# MK1.net
KiCad netlist of a schematic drawn in Altium Designer
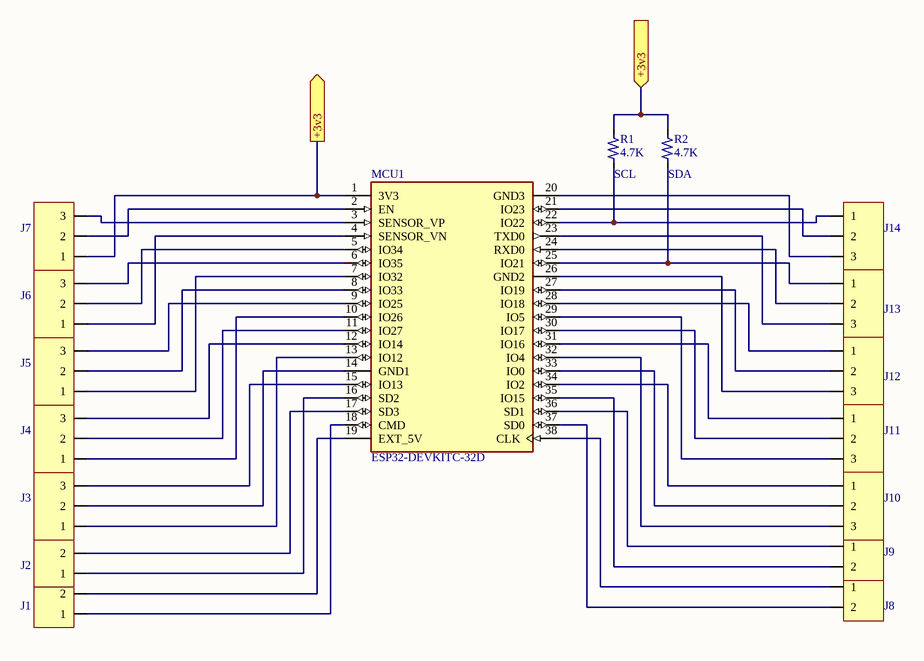
[diagram p0: MK1.SchDoc]

(export (version "E")
  (design (tool "Eeschema 10.0.6"))
  (components
    (comp (ref "J1")
      (value "~")
      (footprint "TB_200Mil 2 P")
      (libsource (lib "Library Connector") (part "TB 2 PIN"))
    )
    (comp (ref "J2")
      (value "~")
      (footprint "TB_200Mil 2 P")
      (libsource (lib "Library Connector") (part "TB 2 PIN"))
    )
    (comp (ref "J3") (value "~") (footprint "TB_200Mil 3 P") (libsource (lib "") (part "TB 3 PIN_1")))
    (comp (ref "J4") (value "~") (footprint "TB_200Mil 3 P") (libsource (lib "") (part "TB 3 PIN_1")))
    (comp (ref "J5") (value "~") (footprint "TB_200Mil 3 P") (libsource (lib "") (part "TB 3 PIN_1")))
    (comp (ref "J6") (value "~") (footprint "TB_200Mil 3 P") (libsource (lib "") (part "TB 3 PIN_1")))
    (comp (ref "J7") (value "~") (footprint "TB_200Mil 3 P") (libsource (lib "") (part "TB 3 PIN_1")))
    (comp (ref "J8") (value "~") (footprint "TB_200Mil 2 P") (libsource (lib "") (part "TB 2 PIN_1")))
    (comp (ref "J9") (value "~") (footprint "TB_200Mil 2 P") (libsource (lib "") (part "TB 2 PIN_1")))
    (comp (ref "J10")
      (value "~")
      (footprint "TB_200Mil 3 P")
      (libsource (lib "Library Connector") (part "TB 3 PIN"))
    )
    (comp (ref "J11")
      (value "~")
      (footprint "TB_200Mil 3 P")
      (libsource (lib "Library Connector") (part "TB 3 PIN"))
    )
    (comp (ref "J12")
      (value "~")
      (footprint "TB_200Mil 3 P")
      (libsource (lib "Library Connector") (part "TB 3 PIN"))
    )
    (comp (ref "J13")
      (value "~")
      (footprint "TB_200Mil 3 P")
      (libsource (lib "Library Connector") (part "TB 3 PIN"))
    )
    (comp (ref "J14")
      (value "~")
      (footprint "TB_200Mil 3 P")
      (libsource (lib "Library Connector") (part "TB 3 PIN"))
    )
    (comp (ref "MCU1")
      (value "ESP32-DEVKITC-32D")
      (footprint "MODULE_ESP32-DEVKITC-32D")
      (description "EVAL BOARD FOR ESP-WROOM-32")
      (fields (field (name "MF") "Espressif Systems"))
      (libsource (lib "ESP32-DEVKITC-32D") (part "ESP32-DEVKITC-32D"))
    )
    (comp (ref "R1") (value "4.7K") (footprint "4.7K") (libsource (lib "Library 0.25w 1_") (part "4.7K")))
    (comp (ref "R2") (value "4.7K") (footprint "4.7K") (libsource (lib "Library 0.25w 1_") (part "4.7K")))
  )
  (nets
    (net (code "1") (name "/+3v3") (class "Default")
      (node (ref "J7") (pin "1") (pinfunction "1_1") (pintype "passive"))
      (node (ref "MCU1") (pin "1") (pinfunction "3V3_1") (pintype "power_in"))
      (node (ref "R1") (pin "2") (pintype "passive"))
      (node (ref "R2") (pin "2") (pintype "passive"))
    )
    (net (code "2") (name "Net-(MCU1-CLK)") (class "Default")
      (node (ref "J8") (pin "1") (pinfunction "1_1") (pintype "passive"))
      (node (ref "MCU1") (pin "38") (pinfunction "CLK_38") (pintype "input"))
    )
    (net (code "3") (name "Net-(MCU1-CMD)") (class "Default")
      (node (ref "J1") (pin "1") (pinfunction "1_1") (pintype "passive"))
      (node (ref "MCU1") (pin "18") (pinfunction "CMD_18") (pintype "bidirectional"))
    )
    (net (code "4") (name "Net-(MCU1-EN)") (class "Default")
      (node (ref "J7") (pin "2") (pinfunction "2_2") (pintype "passive"))
      (node (ref "MCU1") (pin "2") (pinfunction "EN_2") (pintype "input"))
    )
    (net (code "5") (name "Net-(MCU1-EXT_5V)") (class "Default")
      (node (ref "J1") (pin "2") (pinfunction "2_2") (pintype "passive"))
      (node (ref "MCU1") (pin "19") (pinfunction "EXT_5V_19") (pintype "power_in"))
    )
    (net (code "6") (name "Net-(MCU1-GND1)") (class "Default")
      (node (ref "J3") (pin "2") (pinfunction "2_2") (pintype "passive"))
      (node (ref "MCU1") (pin "14") (pinfunction "GND1_14") (pintype "power_in"))
    )
    (net (code "7") (name "Net-(MCU1-GND2)") (class "Default")
      (node (ref "J12") (pin "3") (pinfunction "3_3") (pintype "passive"))
      (node (ref "MCU1") (pin "26") (pinfunction "GND2_26") (pintype "power_in"))
    )
    (net (code "8") (name "Net-(MCU1-GND3)") (class "Default")
      (node (ref "J14") (pin "3") (pinfunction "3_3") (pintype "passive"))
      (node (ref "MCU1") (pin "20") (pinfunction "GND3_20") (pintype "power_in"))
    )
    (net (code "9") (name "Net-(MCU1-IO0)") (class "Default")
      (node (ref "J10") (pin "2") (pinfunction "2_2") (pintype "passive"))
      (node (ref "MCU1") (pin "33") (pinfunction "IO0_33") (pintype "bidirectional"))
    )
    (net (code "10") (name "Net-(MCU1-IO2)") (class "Default")
      (node (ref "J10") (pin "1") (pinfunction "1_1") (pintype "passive"))
      (node (ref "MCU1") (pin "34") (pinfunction "IO2_34") (pintype "bidirectional"))
    )
    (net (code "11") (name "Net-(MCU1-IO4)") (class "Default")
      (node (ref "J10") (pin "3") (pinfunction "3_3") (pintype "passive"))
      (node (ref "MCU1") (pin "32") (pinfunction "IO4_32") (pintype "bidirectional"))
    )
    (net (code "12") (name "Net-(MCU1-IO5)") (class "Default")
      (node (ref "J11") (pin "3") (pinfunction "3_3") (pintype "passive"))
      (node (ref "MCU1") (pin "29") (pinfunction "IO5_29") (pintype "bidirectional"))
    )
    (net (code "13") (name "Net-(MCU1-IO12)") (class "Default")
      (node (ref "J3") (pin "1") (pinfunction "1_1") (pintype "passive"))
      (node (ref "MCU1") (pin "13") (pinfunction "IO12_13") (pintype "bidirectional"))
    )
    (net (code "14") (name "Net-(MCU1-IO13)") (class "Default")
      (node (ref "J3") (pin "3") (pinfunction "3_3") (pintype "passive"))
      (node (ref "MCU1") (pin "15") (pinfunction "IO13_15") (pintype "bidirectional"))
    )
    (net (code "15") (name "Net-(MCU1-IO14)") (class "Default")
      (node (ref "J4") (pin "3") (pinfunction "3_3") (pintype "passive"))
      (node (ref "MCU1") (pin "12") (pinfunction "IO14_12") (pintype "bidirectional"))
    )
    (net (code "16") (name "Net-(MCU1-IO15)") (class "Default")
      (node (ref "J9") (pin "2") (pinfunction "2_2") (pintype "passive"))
      (node (ref "MCU1") (pin "35") (pinfunction "IO15_35") (pintype "bidirectional"))
    )
    (net (code "17") (name "Net-(MCU1-IO16)") (class "Default")
      (node (ref "J11") (pin "1") (pinfunction "1_1") (pintype "passive"))
      (node (ref "MCU1") (pin "31") (pinfunction "IO16_31") (pintype "bidirectional"))
    )
    (net (code "18") (name "Net-(MCU1-IO17)") (class "Default")
      (node (ref "J11") (pin "2") (pinfunction "2_2") (pintype "passive"))
      (node (ref "MCU1") (pin "30") (pinfunction "IO17_30") (pintype "bidirectional"))
    )
    (net (code "19") (name "Net-(MCU1-IO18)") (class "Default")
      (node (ref "J12") (pin "1") (pinfunction "1_1") (pintype "passive"))
      (node (ref "MCU1") (pin "28") (pinfunction "IO18_28") (pintype "bidirectional"))
    )
    (net (code "20") (name "Net-(MCU1-IO19)") (class "Default")
      (node (ref "J12") (pin "2") (pinfunction "2_2") (pintype "passive"))
      (node (ref "MCU1") (pin "27") (pinfunction "IO19_27") (pintype "bidirectional"))
    )
    (net (code "21") (name "Net-(MCU1-IO21)") (class "Default")
      (node (ref "J13") (pin "1") (pinfunction "1_1") (pintype "passive"))
      (node (ref "MCU1") (pin "25") (pinfunction "IO21_25") (pintype "bidirectional"))
      (node (ref "R2") (pin "1") (pintype "passive"))
    )
    (net (code "22") (name "Net-(MCU1-IO22)") (class "Default")
      (node (ref "J14") (pin "1") (pinfunction "1_1") (pintype "passive"))
      (node (ref "MCU1") (pin "22") (pinfunction "IO22_22") (pintype "bidirectional"))
      (node (ref "R1") (pin "1") (pintype "passive"))
    )
    (net (code "23") (name "Net-(MCU1-IO23)") (class "Default")
      (node (ref "J14") (pin "2") (pinfunction "2_2") (pintype "passive"))
      (node (ref "MCU1") (pin "21") (pinfunction "IO23_21") (pintype "bidirectional"))
    )
    (net (code "24") (name "Net-(MCU1-IO25)") (class "Default")
      (node (ref "J5") (pin "3") (pinfunction "3_3") (pintype "passive"))
      (node (ref "MCU1") (pin "9") (pinfunction "IO25_9") (pintype "bidirectional"))
    )
    (net (code "25") (name "Net-(MCU1-IO26)") (class "Default")
      (node (ref "J4") (pin "1") (pinfunction "1_1") (pintype "passive"))
      (node (ref "MCU1") (pin "10") (pinfunction "IO26_10") (pintype "bidirectional"))
    )
    (net (code "26") (name "Net-(MCU1-IO27)") (class "Default")
      (node (ref "J4") (pin "2") (pinfunction "2_2") (pintype "passive"))
      (node (ref "MCU1") (pin "11") (pinfunction "IO27_11") (pintype "bidirectional"))
    )
    (net (code "27") (name "Net-(MCU1-IO32)") (class "Default")
      (node (ref "J5") (pin "1") (pinfunction "1_1") (pintype "passive"))
      (node (ref "MCU1") (pin "7") (pinfunction "IO32_7") (pintype "bidirectional"))
    )
    (net (code "28") (name "Net-(MCU1-IO33)") (class "Default")
      (node (ref "J5") (pin "2") (pinfunction "2_2") (pintype "passive"))
      (node (ref "MCU1") (pin "8") (pinfunction "IO33_8") (pintype "bidirectional"))
    )
    (net (code "29") (name "Net-(MCU1-IO34)") (class "Default")
      (node (ref "J6") (pin "2") (pinfunction "2_2") (pintype "passive"))
      (node (ref "MCU1") (pin "5") (pinfunction "IO34_5") (pintype "bidirectional"))
    )
    (net (code "30") (name "Net-(MCU1-IO35)") (class "Default")
      (node (ref "J6") (pin "3") (pinfunction "3_3") (pintype "passive"))
      (node (ref "MCU1") (pin "6") (pinfunction "IO35_6") (pintype "bidirectional"))
    )
    (net (code "31") (name "Net-(MCU1-RXD0)") (class "Default")
      (node (ref "J13") (pin "2") (pinfunction "2_2") (pintype "passive"))
      (node (ref "MCU1") (pin "24") (pinfunction "RXD0_24") (pintype "input"))
    )
    (net (code "32") (name "Net-(MCU1-SD0)") (class "Default")
      (node (ref "J8") (pin "2") (pinfunction "2_2") (pintype "passive"))
      (node (ref "MCU1") (pin "37") (pinfunction "SD0_37") (pintype "bidirectional"))
    )
    (net (code "33") (name "Net-(MCU1-SD1)") (class "Default")
      (node (ref "J9") (pin "1") (pinfunction "1_1") (pintype "passive"))
      (node (ref "MCU1") (pin "36") (pinfunction "SD1_36") (pintype "bidirectional"))
    )
    (net (code "34") (name "Net-(MCU1-SD2)") (class "Default")
      (node (ref "J2") (pin "1") (pinfunction "1_1") (pintype "passive"))
      (node (ref "MCU1") (pin "16") (pinfunction "SD2_16") (pintype "bidirectional"))
    )
    (net (code "35") (name "Net-(MCU1-SD3)") (class "Default")
      (node (ref "J2") (pin "2") (pinfunction "2_2") (pintype "passive"))
      (node (ref "MCU1") (pin "17") (pinfunction "SD3_17") (pintype "bidirectional"))
    )
    (net (code "36") (name "Net-(MCU1-SENSOR_VN)") (class "Default")
      (node (ref "J6") (pin "1") (pinfunction "1_1") (pintype "passive"))
      (node (ref "MCU1") (pin "4") (pinfunction "SENSOR_VN_4") (pintype "input"))
    )
    (net (code "37") (name "Net-(MCU1-SENSOR_VP)") (class "Default")
      (node (ref "J7") (pin "3") (pinfunction "3_3") (pintype "passive"))
      (node (ref "MCU1") (pin "3") (pinfunction "SENSOR_VP_3") (pintype "input"))
    )
    (net (code "38") (name "Net-(MCU1-TXD0)") (class "Default")
      (node (ref "J13") (pin "3") (pinfunction "3_3") (pintype "passive"))
      (node (ref "MCU1") (pin "23") (pinfunction "TXD0_23") (pintype "output"))
    )
  )
)
